# ADC.net
KiCad netlist of a schematic drawn in Altium Designer
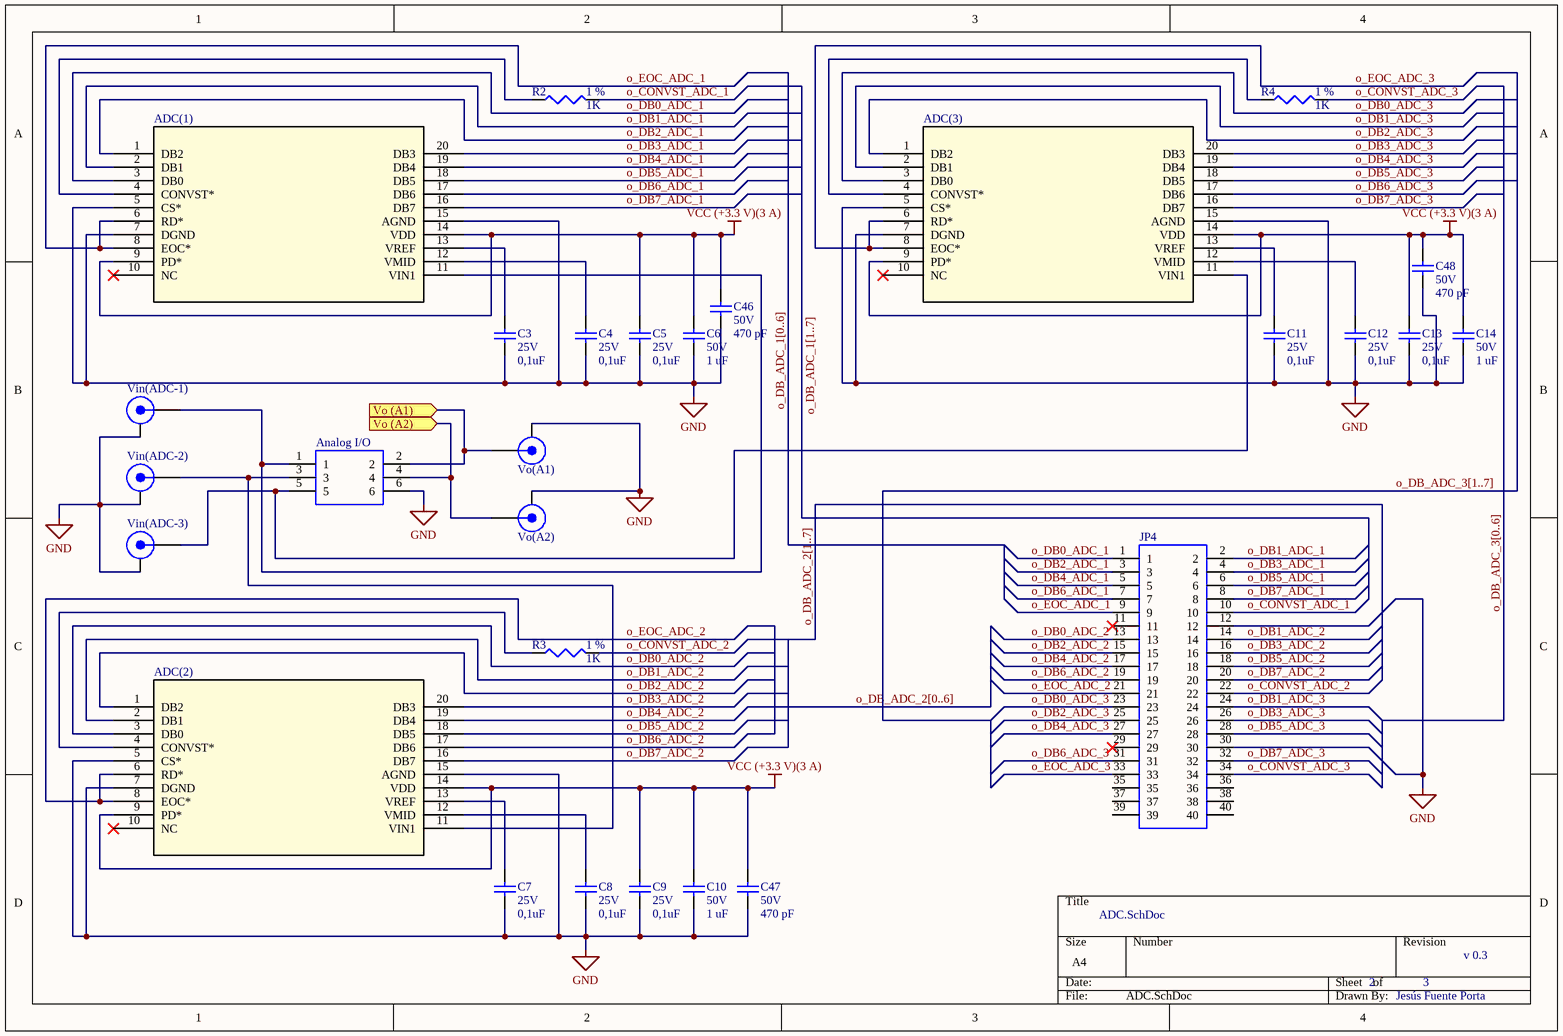
[diagram p0: ADC.SchDoc]

(export (version "E")
  (design (tool "Eeschema 10.0.6"))
  (components
    (comp (ref "ADC(1)")
      (value "AD7822BR")
      (footprint "RW_20-M (AD7822BR)")
      (description "1-Channel Single ADC Semiflash 2Msps 8-bit Parallel 20-Pin SOIC W Tube")
      (libsource (lib "ADC Library_Schematic Symbols") (part "AD7822BR"))
    )
    (comp (ref "ADC(2)")
      (value "AD7822BR")
      (footprint "RW_20-M (AD7822BR)")
      (description "1-Channel Single ADC Semiflash 2Msps 8-bit Parallel 20-Pin SOIC W Tube")
      (libsource (lib "ADC Library_Schematic Symbols") (part "AD7822BR"))
    )
    (comp (ref "ADC(3)")
      (value "AD7822BR")
      (footprint "RW_20-M (AD7822BR)")
      (description "1-Channel Single ADC Semiflash 2Msps 8-bit Parallel 20-Pin SOIC W Tube")
      (libsource (lib "ADC Library_Schematic Symbols") (part "AD7822BR"))
    )
    (comp (ref "Analog I/O")
      (value "IDC Connector_6p")
      (footprint "IDC Connector - 6 pins")
      (fields (field (name "RS PART NUMBER") "6257296"))
      (libsource (lib "ADC Library_Schematic Symbols") (part "IDC Connector_6p"))
    )
    (comp (ref "C3")
      (value "25V")
      (footprint "1206 [Métrica 3216]")
      (fields (field (name "ALTIUM_VALUE") "0,1uF") (field (name "PUBLISHER") "Altium Limited"))
      (libsource (lib "Miscellaneous Devices") (part "Cap Semi"))
    )
    (comp (ref "C4")
      (value "25V")
      (footprint "1206 [Métrica 3216]")
      (fields (field (name "ALTIUM_VALUE") "0,1uF") (field (name "PUBLISHER") "Altium Limited"))
      (libsource (lib "Miscellaneous Devices") (part "Cap Semi"))
    )
    (comp (ref "C5")
      (value "25V")
      (footprint "1206 [Métrica 3216]")
      (fields (field (name "ALTIUM_VALUE") "0,1uF") (field (name "PUBLISHER") "Altium Limited"))
      (libsource (lib "Miscellaneous Devices") (part "Cap Semi"))
    )
    (comp (ref "C6")
      (value "50V")
      (footprint "1206 [Métrica 3216]")
      (fields (field (name "ALTIUM_VALUE") "1 uF") (field (name "PUBLISHER") "Altium Limited"))
      (libsource (lib "Miscellaneous Devices") (part "Cap Semi"))
    )
    (comp (ref "C7")
      (value "25V")
      (footprint "1206 [Métrica 3216]")
      (fields (field (name "ALTIUM_VALUE") "0,1uF") (field (name "PUBLISHER") "Altium Limited"))
      (libsource (lib "Miscellaneous Devices") (part "Cap Semi"))
    )
    (comp (ref "C8")
      (value "25V")
      (footprint "1206 [Métrica 3216]")
      (fields (field (name "ALTIUM_VALUE") "0,1uF") (field (name "PUBLISHER") "Altium Limited"))
      (libsource (lib "Miscellaneous Devices") (part "Cap Semi"))
    )
    (comp (ref "C9")
      (value "25V")
      (footprint "1206 [Métrica 3216]")
      (fields (field (name "ALTIUM_VALUE") "0,1uF") (field (name "PUBLISHER") "Altium Limited"))
      (libsource (lib "Miscellaneous Devices") (part "Cap Semi"))
    )
    (comp (ref "C10")
      (value "50V")
      (footprint "1206 [Métrica 3216]")
      (fields (field (name "ALTIUM_VALUE") "1 uF") (field (name "PUBLISHER") "Altium Limited"))
      (libsource (lib "Miscellaneous Devices") (part "Cap Semi"))
    )
    (comp (ref "C11")
      (value "25V")
      (footprint "1206 [Métrica 3216]")
      (fields (field (name "ALTIUM_VALUE") "0,1uF") (field (name "PUBLISHER") "Altium Limited"))
      (libsource (lib "Miscellaneous Devices") (part "Cap Semi"))
    )
    (comp (ref "C12")
      (value "25V")
      (footprint "1206 [Métrica 3216]")
      (fields (field (name "ALTIUM_VALUE") "0,1uF") (field (name "PUBLISHER") "Altium Limited"))
      (libsource (lib "Miscellaneous Devices") (part "Cap Semi"))
    )
    (comp (ref "C13")
      (value "25V")
      (footprint "1206 [Métrica 3216]")
      (fields (field (name "ALTIUM_VALUE") "0,1uF") (field (name "PUBLISHER") "Altium Limited"))
      (libsource (lib "Miscellaneous Devices") (part "Cap Semi"))
    )
    (comp (ref "C14")
      (value "50V")
      (footprint "1206 [Métrica 3216]")
      (fields (field (name "ALTIUM_VALUE") "1 uF") (field (name "PUBLISHER") "Altium Limited"))
      (libsource (lib "Miscellaneous Devices") (part "Cap Semi"))
    )
    (comp (ref "C46")
      (value "50V")
      (footprint "1206 [Métrica 3216]")
      (fields (field (name "ALTIUM_VALUE") "470 pF") (field (name "PUBLISHER") "Altium Limited"))
      (libsource (lib "Miscellaneous Devices") (part "Cap Semi"))
    )
    (comp (ref "C47")
      (value "50V")
      (footprint "1206 [Métrica 3216]")
      (fields (field (name "ALTIUM_VALUE") "470 pF") (field (name "PUBLISHER") "Altium Limited"))
      (libsource (lib "Miscellaneous Devices") (part "Cap Semi"))
    )
    (comp (ref "C48")
      (value "50V")
      (footprint "1206 [Métrica 3216]")
      (fields (field (name "ALTIUM_VALUE") "470 pF") (field (name "PUBLISHER") "Altium Limited"))
      (libsource (lib "Miscellaneous Devices") (part "Cap Semi"))
    )
    (comp (ref "JP4")
      (value "IDC Connector_40p")
      (footprint "IDC Connector - 40 pins")
      (fields (field (name "RS PART NUMBER") "6257296"))
      (libsource (lib "ADC Library_Schematic Symbols") (part "IDC Connector_40p"))
    )
    (comp (ref "R2")
      (value "1 %")
      (footprint "1206 [Métrica 3216]")
      (fields (field (name "ALTIUM_VALUE") "1K") (field (name "PUBLISHER") "Altium Limited"))
      (libsource (lib "Miscellaneous Devices") (part "Res3"))
    )
    (comp (ref "R3")
      (value "1 %")
      (footprint "1206 [Métrica 3216]")
      (fields (field (name "ALTIUM_VALUE") "1K") (field (name "PUBLISHER") "Altium Limited"))
      (libsource (lib "Miscellaneous Devices") (part "Res3"))
    )
    (comp (ref "R4")
      (value "1 %")
      (footprint "1206 [Métrica 3216]")
      (fields (field (name "ALTIUM_VALUE") "1K") (field (name "PUBLISHER") "Altium Limited"))
      (libsource (lib "Miscellaneous Devices") (part "Res3"))
    )
    (comp (ref "Vin(ADC-1)")
      (value "19S101-40ML5")
      (footprint "ROS-19S101-40ML5_V")
      (libsource (lib "Rosenberger SMP") (part "19S101-40ML5"))
    )
    (comp (ref "Vin(ADC-2)")
      (value "19S101-40ML5")
      (footprint "ROS-19S101-40ML5_V")
      (libsource (lib "Rosenberger SMP") (part "19S101-40ML5"))
    )
    (comp (ref "Vin(ADC-3)")
      (value "19S101-40ML5")
      (footprint "ROS-19S101-40ML5_V")
      (libsource (lib "Rosenberger SMP") (part "19S101-40ML5"))
    )
    (comp (ref "Vo(A1)")
      (value "19S101-40ML5")
      (footprint "ROS-19S101-40ML5_V")
      (libsource (lib "Rosenberger SMP") (part "19S101-40ML5"))
    )
    (comp (ref "Vo(A2)")
      (value "19S101-40ML5")
      (footprint "ROS-19S101-40ML5_V")
      (libsource (lib "Rosenberger SMP") (part "19S101-40ML5"))
    )
  )
  (nets
    (net (code "25") (name "/Vo (A1)") (class "Default")
      (node (ref "Analog I/O") (pin "2") (pinfunction "2_2") (pintype "passive"))
      (node (ref "Vo(A1)") (pin "1") (pinfunction "1_1") (pintype "passive"))
    )
    (net (code "26") (name "/Vo (A2)") (class "Default")
      (node (ref "Analog I/O") (pin "4") (pinfunction "4_4") (pintype "passive"))
      (node (ref "Vo(A2)") (pin "1") (pinfunction "1_1") (pintype "passive"))
    )
    (net (code "27") (name "/o_CONVST_ADC_1") (class "Default")
      (node (ref "JP4") (pin "10") (pinfunction "10_10") (pintype "passive"))
      (node (ref "R2") (pin "2") (pinfunction "2_2") (pintype "passive"))
    )
    (net (code "28") (name "/o_CONVST_ADC_2") (class "Default")
      (node (ref "JP4") (pin "22") (pinfunction "22_22") (pintype "passive"))
      (node (ref "R3") (pin "2") (pinfunction "2_2") (pintype "passive"))
    )
    (net (code "29") (name "/o_CONVST_ADC_3") (class "Default")
      (node (ref "JP4") (pin "34") (pinfunction "34_34") (pintype "passive"))
      (node (ref "R4") (pin "2") (pinfunction "2_2") (pintype "passive"))
    )
    (net (code "30") (name "/o_DB0_ADC_1") (class "Default")
      (node (ref "ADC(1)") (pin "3") (pinfunction "DB0_3") (pintype "passive"))
      (node (ref "JP4") (pin "1") (pinfunction "1_1") (pintype "passive"))
    )
    (net (code "31") (name "/o_DB0_ADC_2") (class "Default")
      (node (ref "ADC(2)") (pin "3") (pinfunction "DB0_3") (pintype "passive"))
      (node (ref "JP4") (pin "13") (pinfunction "13_13") (pintype "passive"))
    )
    (net (code "32") (name "/o_DB0_ADC_3") (class "Default")
      (node (ref "ADC(3)") (pin "3") (pinfunction "DB0_3") (pintype "passive"))
      (node (ref "JP4") (pin "23") (pinfunction "23_23") (pintype "passive"))
    )
    (net (code "33") (name "/o_DB1_ADC_1") (class "Default")
      (node (ref "ADC(1)") (pin "2") (pinfunction "DB1_2") (pintype "passive"))
      (node (ref "JP4") (pin "2") (pinfunction "2_2") (pintype "passive"))
    )
    (net (code "34") (name "/o_DB1_ADC_2") (class "Default")
      (node (ref "ADC(2)") (pin "2") (pinfunction "DB1_2") (pintype "passive"))
      (node (ref "JP4") (pin "14") (pinfunction "14_14") (pintype "passive"))
    )
    (net (code "35") (name "/o_DB1_ADC_3") (class "Default")
      (node (ref "ADC(3)") (pin "2") (pinfunction "DB1_2") (pintype "passive"))
      (node (ref "JP4") (pin "24") (pinfunction "24_24") (pintype "passive"))
    )
    (net (code "36") (name "/o_DB2_ADC_1") (class "Default")
      (node (ref "ADC(1)") (pin "1") (pinfunction "DB2_1") (pintype "passive"))
      (node (ref "JP4") (pin "3") (pinfunction "3_3") (pintype "passive"))
    )
    (net (code "37") (name "/o_DB2_ADC_2") (class "Default")
      (node (ref "ADC(2)") (pin "1") (pinfunction "DB2_1") (pintype "passive"))
      (node (ref "JP4") (pin "15") (pinfunction "15_15") (pintype "passive"))
    )
    (net (code "38") (name "/o_DB2_ADC_3") (class "Default")
      (node (ref "ADC(3)") (pin "1") (pinfunction "DB2_1") (pintype "passive"))
      (node (ref "JP4") (pin "25") (pinfunction "25_25") (pintype "passive"))
    )
    (net (code "39") (name "/o_DB3_ADC_1") (class "Default")
      (node (ref "ADC(1)") (pin "20") (pinfunction "DB3_20") (pintype "passive"))
      (node (ref "JP4") (pin "4") (pinfunction "4_4") (pintype "passive"))
    )
    (net (code "40") (name "/o_DB3_ADC_2") (class "Default")
      (node (ref "ADC(2)") (pin "20") (pinfunction "DB3_20") (pintype "passive"))
      (node (ref "JP4") (pin "16") (pinfunction "16_16") (pintype "passive"))
    )
    (net (code "41") (name "/o_DB3_ADC_3") (class "Default")
      (node (ref "ADC(3)") (pin "20") (pinfunction "DB3_20") (pintype "passive"))
      (node (ref "JP4") (pin "26") (pinfunction "26_26") (pintype "passive"))
    )
    (net (code "42") (name "/o_DB4_ADC_1") (class "Default")
      (node (ref "ADC(1)") (pin "19") (pinfunction "DB4_19") (pintype "passive"))
      (node (ref "JP4") (pin "5") (pinfunction "5_5") (pintype "passive"))
    )
    (net (code "43") (name "/o_DB4_ADC_2") (class "Default")
      (node (ref "ADC(2)") (pin "19") (pinfunction "DB4_19") (pintype "passive"))
      (node (ref "JP4") (pin "17") (pinfunction "17_17") (pintype "passive"))
    )
    (net (code "44") (name "/o_DB4_ADC_3") (class "Default")
      (node (ref "ADC(3)") (pin "19") (pinfunction "DB4_19") (pintype "passive"))
      (node (ref "JP4") (pin "27") (pinfunction "27_27") (pintype "passive"))
    )
    (net (code "45") (name "/o_DB5_ADC_1") (class "Default")
      (node (ref "ADC(1)") (pin "18") (pinfunction "DB5_18") (pintype "passive"))
      (node (ref "JP4") (pin "6") (pinfunction "6_6") (pintype "passive"))
    )
    (net (code "46") (name "/o_DB5_ADC_2") (class "Default")
      (node (ref "ADC(2)") (pin "18") (pinfunction "DB5_18") (pintype "passive"))
      (node (ref "JP4") (pin "18") (pinfunction "18_18") (pintype "passive"))
    )
    (net (code "47") (name "/o_DB5_ADC_3") (class "Default")
      (node (ref "ADC(3)") (pin "18") (pinfunction "DB5_18") (pintype "passive"))
      (node (ref "JP4") (pin "28") (pinfunction "28_28") (pintype "passive"))
    )
    (net (code "48") (name "/o_DB6_ADC_1") (class "Default")
      (node (ref "ADC(1)") (pin "17") (pinfunction "DB6_17") (pintype "passive"))
      (node (ref "JP4") (pin "7") (pinfunction "7_7") (pintype "passive"))
    )
    (net (code "49") (name "/o_DB6_ADC_2") (class "Default")
      (node (ref "ADC(2)") (pin "17") (pinfunction "DB6_17") (pintype "passive"))
      (node (ref "JP4") (pin "19") (pinfunction "19_19") (pintype "passive"))
    )
    (net (code "50") (name "/o_DB6_ADC_3") (class "Default")
      (node (ref "ADC(3)") (pin "17") (pinfunction "DB6_17") (pintype "passive"))
      (node (ref "JP4") (pin "31") (pinfunction "31_31") (pintype "passive"))
    )
    (net (code "51") (name "/o_DB7_ADC_1") (class "Default")
      (node (ref "ADC(1)") (pin "16") (pinfunction "DB7_16") (pintype "passive"))
      (node (ref "JP4") (pin "8") (pinfunction "8_8") (pintype "passive"))
    )
    (net (code "52") (name "/o_DB7_ADC_2") (class "Default")
      (node (ref "ADC(2)") (pin "16") (pinfunction "DB7_16") (pintype "passive"))
      (node (ref "JP4") (pin "20") (pinfunction "20_20") (pintype "passive"))
    )
    (net (code "53") (name "/o_DB7_ADC_3") (class "Default")
      (node (ref "ADC(3)") (pin "16") (pinfunction "DB7_16") (pintype "passive"))
      (node (ref "JP4") (pin "32") (pinfunction "32_32") (pintype "passive"))
    )
    (net (code "60") (name "/o_EOC_ADC_1") (class "Default")
      (node (ref "ADC(1)") (pin "6") (pinfunction "RD*_6") (pintype "passive"))
      (node (ref "ADC(1)") (pin "8") (pinfunction "EOC*_8") (pintype "passive"))
      (node (ref "JP4") (pin "9") (pinfunction "9_9") (pintype "passive"))
    )
    (net (code "61") (name "/o_EOC_ADC_2") (class "Default")
      (node (ref "ADC(2)") (pin "6") (pinfunction "RD*_6") (pintype "passive"))
      (node (ref "ADC(2)") (pin "8") (pinfunction "EOC*_8") (pintype "passive"))
      (node (ref "JP4") (pin "21") (pinfunction "21_21") (pintype "passive"))
    )
    (net (code "62") (name "/o_EOC_ADC_3") (class "Default")
      (node (ref "ADC(3)") (pin "6") (pinfunction "RD*_6") (pintype "passive"))
      (node (ref "ADC(3)") (pin "8") (pinfunction "EOC*_8") (pintype "passive"))
      (node (ref "JP4") (pin "33") (pinfunction "33_33") (pintype "passive"))
    )
    (net (code "63") (name "GND") (class "Default")
      (node (ref "ADC(1)") (pin "15") (pinfunction "AGND_15") (pintype "passive"))
      (node (ref "ADC(1)") (pin "5") (pinfunction "CS*_5") (pintype "passive"))
      (node (ref "ADC(1)") (pin "7") (pinfunction "DGND_7") (pintype "passive"))
      (node (ref "ADC(2)") (pin "15") (pinfunction "AGND_15") (pintype "passive"))
      (node (ref "ADC(2)") (pin "5") (pinfunction "CS*_5") (pintype "passive"))
      (node (ref "ADC(2)") (pin "7") (pinfunction "DGND_7") (pintype "passive"))
      (node (ref "ADC(3)") (pin "15") (pinfunction "AGND_15") (pintype "passive"))
      (node (ref "ADC(3)") (pin "5") (pinfunction "CS*_5") (pintype "passive"))
      (node (ref "ADC(3)") (pin "7") (pinfunction "DGND_7") (pintype "passive"))
      (node (ref "Analog I/O") (pin "6") (pinfunction "6_6") (pintype "passive"))
      (node (ref "C10") (pin "1") (pinfunction "1_1") (pintype "passive"))
      (node (ref "C11") (pin "1") (pinfunction "1_1") (pintype "passive"))
      (node (ref "C12") (pin "1") (pinfunction "1_1") (pintype "passive"))
      (node (ref "C13") (pin "1") (pinfunction "1_1") (pintype "passive"))
      (node (ref "C14") (pin "1") (pinfunction "1_1") (pintype "passive"))
      (node (ref "C3") (pin "1") (pinfunction "1_1") (pintype "passive"))
      (node (ref "C4") (pin "1") (pinfunction "1_1") (pintype "passive"))
      (node (ref "C46") (pin "1") (pinfunction "1_1") (pintype "passive"))
      (node (ref "C47") (pin "1") (pinfunction "1_1") (pintype "passive"))
      (node (ref "C48") (pin "1") (pinfunction "1_1") (pintype "passive"))
      (node (ref "C5") (pin "1") (pinfunction "1_1") (pintype "passive"))
      (node (ref "C6") (pin "1") (pinfunction "1_1") (pintype "passive"))
      (node (ref "C7") (pin "1") (pinfunction "1_1") (pintype "passive"))
      (node (ref "C8") (pin "1") (pinfunction "1_1") (pintype "passive"))
      (node (ref "C9") (pin "1") (pinfunction "1_1") (pintype "passive"))
      (node (ref "JP4") (pin "12") (pinfunction "12_12") (pintype "passive"))
      (node (ref "JP4") (pin "30") (pinfunction "30_30") (pintype "passive"))
      (node (ref "Vin(ADC-1)") (pin "MP") (pinfunction "MP_MP") (pintype "passive"))
      (node (ref "Vin(ADC-2)") (pin "MP") (pinfunction "MP_MP") (pintype "passive"))
      (node (ref "Vin(ADC-3)") (pin "MP") (pinfunction "MP_MP") (pintype "passive"))
      (node (ref "Vo(A1)") (pin "MP") (pinfunction "MP_MP") (pintype "passive"))
      (node (ref "Vo(A2)") (pin "MP") (pinfunction "MP_MP") (pintype "passive"))
    )
    (net (code "64") (name "Net-(ADC(1)-CONVST*)") (class "Default")
      (node (ref "ADC(1)") (pin "4") (pinfunction "CONVST*_4") (pintype "passive"))
      (node (ref "R2") (pin "1") (pinfunction "1_1") (pintype "passive"))
    )
    (net (code "65") (name "Net-(ADC(1)-VIN1)") (class "Default")
      (node (ref "ADC(1)") (pin "11") (pinfunction "VIN1_11") (pintype "passive"))
      (node (ref "Analog I/O") (pin "1") (pinfunction "1_1") (pintype "passive"))
      (node (ref "Vin(ADC-1)") (pin "1") (pinfunction "1_1") (pintype "passive"))
    )
    (net (code "66") (name "Net-(ADC(1)-VMID)") (class "Default")
      (node (ref "ADC(1)") (pin "12") (pinfunction "VMID_12") (pintype "passive"))
      (node (ref "C4") (pin "2") (pinfunction "2_2") (pintype "passive"))
    )
    (net (code "67") (name "Net-(ADC(1)-VREF)") (class "Default")
      (node (ref "ADC(1)") (pin "13") (pinfunction "VREF_13") (pintype "passive"))
      (node (ref "C3") (pin "2") (pinfunction "2_2") (pintype "passive"))
    )
    (net (code "68") (name "Net-(ADC(2)-CONVST*)") (class "Default")
      (node (ref "ADC(2)") (pin "4") (pinfunction "CONVST*_4") (pintype "passive"))
      (node (ref "R3") (pin "1") (pinfunction "1_1") (pintype "passive"))
    )
    (net (code "69") (name "Net-(ADC(2)-VIN1)") (class "Default")
      (node (ref "ADC(2)") (pin "11") (pinfunction "VIN1_11") (pintype "passive"))
      (node (ref "Analog I/O") (pin "3") (pinfunction "3_3") (pintype "passive"))
      (node (ref "Vin(ADC-2)") (pin "1") (pinfunction "1_1") (pintype "passive"))
    )
    (net (code "70") (name "Net-(ADC(2)-VMID)") (class "Default")
      (node (ref "ADC(2)") (pin "12") (pinfunction "VMID_12") (pintype "passive"))
      (node (ref "C8") (pin "2") (pinfunction "2_2") (pintype "passive"))
    )
    (net (code "71") (name "Net-(ADC(2)-VREF)") (class "Default")
      (node (ref "ADC(2)") (pin "13") (pinfunction "VREF_13") (pintype "passive"))
      (node (ref "C7") (pin "2") (pinfunction "2_2") (pintype "passive"))
    )
    (net (code "72") (name "Net-(ADC(3)-CONVST*)") (class "Default")
      (node (ref "ADC(3)") (pin "4") (pinfunction "CONVST*_4") (pintype "passive"))
      (node (ref "R4") (pin "1") (pinfunction "1_1") (pintype "passive"))
    )
    (net (code "73") (name "Net-(ADC(3)-VIN1)") (class "Default")
      (node (ref "ADC(3)") (pin "11") (pinfunction "VIN1_11") (pintype "passive"))
      (node (ref "Analog I/O") (pin "5") (pinfunction "5_5") (pintype "passive"))
      (node (ref "Vin(ADC-3)") (pin "1") (pinfunction "1_1") (pintype "passive"))
    )
    (net (code "74") (name "Net-(ADC(3)-VMID)") (class "Default")
      (node (ref "ADC(3)") (pin "12") (pinfunction "VMID_12") (pintype "passive"))
      (node (ref "C12") (pin "2") (pinfunction "2_2") (pintype "passive"))
    )
    (net (code "75") (name "Net-(ADC(3)-VREF)") (class "Default")
      (node (ref "ADC(3)") (pin "13") (pinfunction "VREF_13") (pintype "passive"))
      (node (ref "C11") (pin "2") (pinfunction "2_2") (pintype "passive"))
    )
    (net (code "76") (name "VCC (+3.3 V)(3 A)") (class "Default")
      (node (ref "ADC(1)") (pin "14") (pinfunction "VDD_14") (pintype "power_in"))
      (node (ref "ADC(1)") (pin "9") (pinfunction "PD*_9") (pintype "passive"))
      (node (ref "ADC(2)") (pin "14") (pinfunction "VDD_14") (pintype "power_in"))
      (node (ref "ADC(2)") (pin "9") (pinfunction "PD*_9") (pintype "passive"))
      (node (ref "ADC(3)") (pin "14") (pinfunction "VDD_14") (pintype "power_in"))
      (node (ref "ADC(3)") (pin "9") (pinfunction "PD*_9") (pintype "passive"))
      (node (ref "C10") (pin "2") (pinfunction "2_2") (pintype "passive"))
      (node (ref "C13") (pin "2") (pinfunction "2_2") (pintype "passive"))
      (node (ref "C14") (pin "2") (pinfunction "2_2") (pintype "passive"))
      (node (ref "C46") (pin "2") (pinfunction "2_2") (pintype "passive"))
      (node (ref "C47") (pin "2") (pinfunction "2_2") (pintype "passive"))
      (node (ref "C48") (pin "2") (pinfunction "2_2") (pintype "passive"))
      (node (ref "C5") (pin "2") (pinfunction "2_2") (pintype "passive"))
      (node (ref "C6") (pin "2") (pinfunction "2_2") (pintype "passive"))
      (node (ref "C9") (pin "2") (pinfunction "2_2") (pintype "passive"))
    )
    (net (code "77") (name "unconnected-(ADC(1)-NC-Pad10)") (class "Default")
      (node (ref "ADC(1)") (pin "10") (pinfunction "NC_10") (pintype "passive+no_connect"))
    )
    (net (code "78") (name "unconnected-(ADC(2)-NC-Pad10)") (class "Default")
      (node (ref "ADC(2)") (pin "10") (pinfunction "NC_10") (pintype "passive+no_connect"))
    )
    (net (code "79") (name "unconnected-(ADC(3)-NC-Pad10)") (class "Default")
      (node (ref "ADC(3)") (pin "10") (pinfunction "NC_10") (pintype "passive+no_connect"))
    )
    (net (code "80") (name "unconnected-(JP4-Pad11)") (class "Default")
      (node (ref "JP4") (pin "11") (pinfunction "11_11") (pintype "passive+no_connect"))
    )
    (net (code "81") (name "unconnected-(JP4-Pad29)") (class "Default")
      (node (ref "JP4") (pin "29") (pinfunction "29_29") (pintype "passive+no_connect"))
    )
    (net (code "82") (name "unconnected-(JP4-Pad35)") (class "Default")
      (node (ref "JP4") (pin "35") (pinfunction "35_35") (pintype "passive"))
    )
    (net (code "83") (name "unconnected-(JP4-Pad36)") (class "Default")
      (node (ref "JP4") (pin "36") (pinfunction "36_36") (pintype "passive"))
    )
    (net (code "84") (name "unconnected-(JP4-Pad37)") (class "Default")
      (node (ref "JP4") (pin "37") (pinfunction "37_37") (pintype "passive"))
    )
    (net (code "85") (name "unconnected-(JP4-Pad38)") (class "Default")
      (node (ref "JP4") (pin "38") (pinfunction "38_38") (pintype "passive"))
    )
    (net (code "86") (name "unconnected-(JP4-Pad39)") (class "Default")
      (node (ref "JP4") (pin "39") (pinfunction "39_39") (pintype "passive"))
    )
    (net (code "87") (name "unconnected-(JP4-Pad40)") (class "Default")
      (node (ref "JP4") (pin "40") (pinfunction "40_40") (pintype "passive"))
    )
  )
)
